# Protocol.net
KiCad netlist of a schematic drawn in Altium Designer
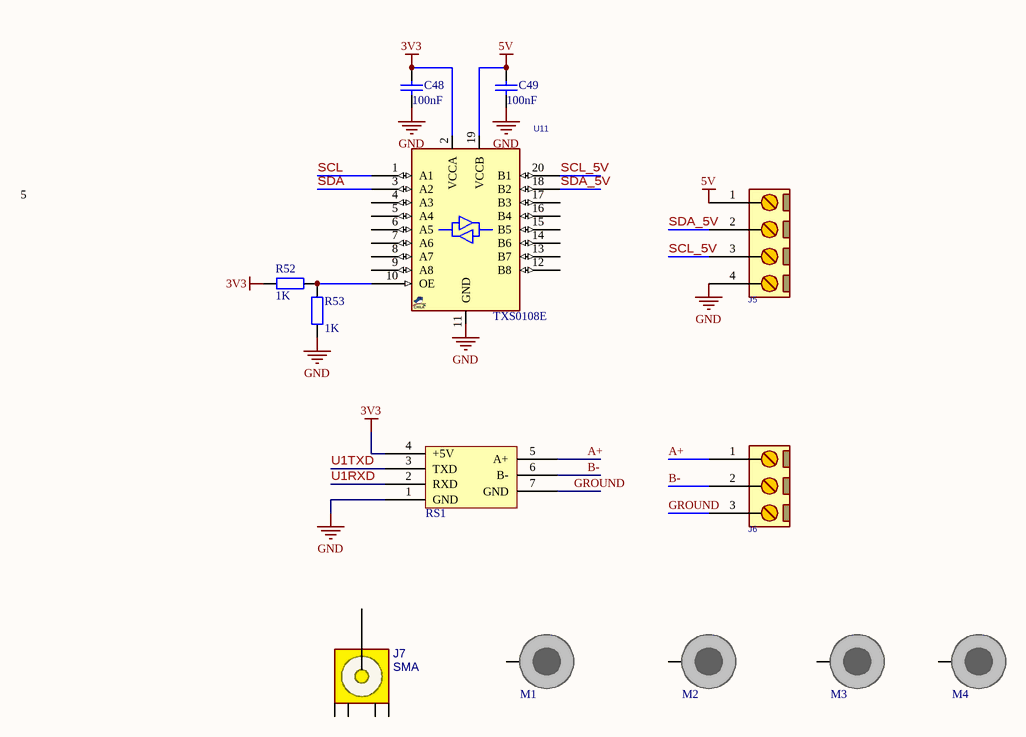
[diagram p0: Protocol.SchDoc]

(export (version "E")
  (design (tool "Eeschema 10.0.6"))
  (components
    (comp (ref "C48")
      (value "100nF_0603_1%")
      (footprint "tu 0603")
      (description "Capacitor, Ceramic, 50V")
      (fields (field (name "MA_HANG") "100nF"))
      (libsource (lib "THU VIEN SCH") (part "Tu 0603 470pF 50V 10%"))
    )
    (comp (ref "C49")
      (value "100nF_0603_1%")
      (footprint "tu 0603")
      (description "Capacitor, Ceramic, 50V")
      (fields (field (name "MA_HANG") "100nF"))
      (libsource (lib "THU VIEN SCH") (part "Tu 0603 470pF 50V 10%"))
    )
    (comp (ref "J5")
      (value "CONN_TB4")
      (footprint "TBB_4")
      (description "CONN, TERMINAL BLOCK, 5.08mm pitch")
      (libsource (lib "AH_Library") (part "CONN_TB4"))
    )
    (comp (ref "J6")
      (value "CONN_TB3")
      (footprint "TBB_3")
      (description "CONN, TERMINAL BLOCK, 5.08mm pitch")
      (libsource (lib "AH_Library") (part "CONN_TB3"))
    )
    (comp (ref "J7")
      (value "SMA")
      (footprint "SMA_RA")
      (description "CONN, RF, SMA, Right Angle")
      (fields (field (name "MANF_P#") "SMA-J-P-H-RA-TH1") (field (name "MANF") "Samtec"))
      (libsource (lib "AH_Library") (part "CONN_RF_SMA_RA"))
    )
    (comp (ref "M1")
      (value "DNP/MH")
      (footprint "SCMH_M3FT")
      (description "SCREW mouting, M3, 3.0mm diameter and 6.0mm, FlatHead")
      (libsource (lib "AH_Library") (part "SCMH_M3FT"))
    )
    (comp (ref "M2")
      (value "DNP/MH")
      (footprint "SCMH_M3FT")
      (description "SCREW mouting, M3, 3.0mm diameter and 6.0mm, FlatHead")
      (libsource (lib "AH_Library") (part "SCMH_M3FT"))
    )
    (comp (ref "M3")
      (value "DNP/MH")
      (footprint "SCMH_M3FT")
      (description "SCREW mouting, M3, 3.0mm diameter and 6.0mm, FlatHead")
      (libsource (lib "AH_Library") (part "SCMH_M3FT"))
    )
    (comp (ref "M4")
      (value "DNP/MH")
      (footprint "SCMH_M3FT")
      (description "SCREW mouting, M3, 3.0mm diameter and 6.0mm, FlatHead")
      (libsource (lib "AH_Library") (part "SCMH_M3FT"))
    )
    (comp (ref "R52")
      (value "1K_0603_1%")
      (footprint "tro smd 0603")
      (description "RES SMD 0603")
      (fields (field (name "MA_HANG") "1K"))
      (libsource (lib "THU VIEN SCH") (part "Tro 0603 5% 10k"))
    )
    (comp (ref "R53")
      (value "1K_0603_1%")
      (footprint "tro smd 0603")
      (description "RES SMD 0603")
      (fields (field (name "MA_HANG") "1K"))
      (libsource (lib "THU VIEN SCH") (part "Tro 0603 5% 10k"))
    )
    (comp (ref "RS1")
      (value "RS485_VISION2")
      (footprint "RS485 - Version2")
      (libsource (lib "TRANTHANHSANG") (part "RS485_VISION2"))
    )
    (comp (ref "U11")
      (value "TXS0108E")
      (footprint "SOG65_20")
      (description "Level Translator, Octal")
      (fields (field (name "MANF") "Texas Instruments") (field (name "MANF_P#") "TXS0108EPWR"))
      (libsource (lib "AH_Library") (part "TXS0108_SSOP20"))
    )
  )
  (nets
    (net (code "1") (name "/A+") (class "Default")
      (node (ref "J6") (pin "1") (pinfunction "1_1") (pintype "passive"))
      (node (ref "RS1") (pin "5") (pinfunction "A+_5") (pintype "passive"))
    )
    (net (code "2") (name "/B-") (class "Default")
      (node (ref "J6") (pin "2") (pinfunction "2_2") (pintype "passive"))
      (node (ref "RS1") (pin "6") (pinfunction "B-_6") (pintype "passive"))
    )
    (net (code "3") (name "/GROUND") (class "Default")
      (node (ref "J6") (pin "3") (pinfunction "3_3") (pintype "passive"))
      (node (ref "RS1") (pin "7") (pinfunction "GND_7") (pintype "passive"))
    )
    (net (code "4") (name "/SCL") (class "Default")
      (node (ref "U11") (pin "1") (pinfunction "A1_1") (pintype "bidirectional"))
    )
    (net (code "5") (name "/SCL_5V") (class "Default")
      (node (ref "J5") (pin "3") (pinfunction "3_3") (pintype "passive"))
      (node (ref "U11") (pin "20") (pinfunction "B1_20") (pintype "bidirectional"))
    )
    (net (code "6") (name "/SDA") (class "Default")
      (node (ref "U11") (pin "3") (pinfunction "A2_3") (pintype "bidirectional"))
    )
    (net (code "7") (name "/SDA_5V") (class "Default")
      (node (ref "J5") (pin "2") (pinfunction "2_2") (pintype "passive"))
      (node (ref "U11") (pin "18") (pinfunction "B2_18") (pintype "bidirectional"))
    )
    (net (code "8") (name "/U1RXD") (class "Default")
      (node (ref "RS1") (pin "2") (pinfunction "RXD_2") (pintype "passive"))
    )
    (net (code "9") (name "/U1TXD") (class "Default")
      (node (ref "RS1") (pin "3") (pinfunction "TXD_3") (pintype "passive"))
    )
    (net (code "10") (name "3V3") (class "Default")
      (node (ref "C48") (pin "1") (pinfunction "1_1") (pintype "passive"))
      (node (ref "R52") (pin "2") (pinfunction "2_2") (pintype "passive"))
      (node (ref "RS1") (pin "4") (pinfunction "+5V_4") (pintype "passive"))
      (node (ref "U11") (pin "2") (pinfunction "VCCA_2") (pintype "power_in"))
    )
    (net (code "11") (name "5V") (class "Default")
      (node (ref "C49") (pin "1") (pinfunction "1_1") (pintype "passive"))
      (node (ref "J5") (pin "1") (pinfunction "1_1") (pintype "passive"))
      (node (ref "U11") (pin "19") (pinfunction "VCCB_19") (pintype "power_in"))
    )
    (net (code "12") (name "GND") (class "Default")
      (node (ref "C48") (pin "2") (pinfunction "2_2") (pintype "passive"))
      (node (ref "C49") (pin "2") (pinfunction "2_2") (pintype "passive"))
      (node (ref "J5") (pin "4") (pinfunction "4_4") (pintype "passive"))
      (node (ref "R53") (pin "1") (pinfunction "1_1") (pintype "passive"))
      (node (ref "RS1") (pin "1") (pinfunction "GND_1") (pintype "passive"))
      (node (ref "U11") (pin "11") (pinfunction "GND_11") (pintype "power_in"))
    )
    (net (code "13") (name "Net-(U11-OE)") (class "Default")
      (node (ref "R52") (pin "1") (pinfunction "1_1") (pintype "passive"))
      (node (ref "R53") (pin "2") (pinfunction "2_2") (pintype "passive"))
      (node (ref "U11") (pin "10") (pinfunction "OE_10") (pintype "input"))
    )
    (net (code "14") (name "unconnected-(J7-G1-Pad2)") (class "Default")
      (node (ref "J7") (pin "2") (pinfunction "G1_2") (pintype "passive"))
    )
    (net (code "15") (name "unconnected-(J7-G2-Pad3)") (class "Default")
      (node (ref "J7") (pin "3") (pinfunction "G2_3") (pintype "passive"))
    )
    (net (code "16") (name "unconnected-(J7-G3-Pad4)") (class "Default")
      (node (ref "J7") (pin "4") (pinfunction "G3_4") (pintype "passive"))
    )
    (net (code "17") (name "unconnected-(J7-G4-Pad5)") (class "Default")
      (node (ref "J7") (pin "5") (pinfunction "G4_5") (pintype "passive"))
    )
    (net (code "18") (name "unconnected-(J7-SIG-Pad1)") (class "Default")
      (node (ref "J7") (pin "1") (pinfunction "SIG_1") (pintype "passive"))
    )
    (net (code "19") (name "unconnected-(M1-Pad1)") (class "Default")
      (node (ref "M1") (pin "1") (pinfunction "1_1") (pintype "passive"))
    )
    (net (code "20") (name "unconnected-(M2-Pad1)") (class "Default")
      (node (ref "M2") (pin "1") (pinfunction "1_1") (pintype "passive"))
    )
    (net (code "21") (name "unconnected-(M3-Pad1)") (class "Default")
      (node (ref "M3") (pin "1") (pinfunction "1_1") (pintype "passive"))
    )
    (net (code "22") (name "unconnected-(M4-Pad1)") (class "Default")
      (node (ref "M4") (pin "1") (pinfunction "1_1") (pintype "passive"))
    )
    (net (code "23") (name "unconnected-(U11-A3-Pad4)") (class "Default")
      (node (ref "U11") (pin "4") (pinfunction "A3_4") (pintype "bidirectional"))
    )
    (net (code "24") (name "unconnected-(U11-A4-Pad5)") (class "Default")
      (node (ref "U11") (pin "5") (pinfunction "A4_5") (pintype "bidirectional"))
    )
    (net (code "25") (name "unconnected-(U11-A5-Pad6)") (class "Default")
      (node (ref "U11") (pin "6") (pinfunction "A5_6") (pintype "bidirectional"))
    )
    (net (code "26") (name "unconnected-(U11-A6-Pad7)") (class "Default")
      (node (ref "U11") (pin "7") (pinfunction "A6_7") (pintype "bidirectional"))
    )
    (net (code "27") (name "unconnected-(U11-A7-Pad8)") (class "Default")
      (node (ref "U11") (pin "8") (pinfunction "A7_8") (pintype "bidirectional"))
    )
    (net (code "28") (name "unconnected-(U11-A8-Pad9)") (class "Default")
      (node (ref "U11") (pin "9") (pinfunction "A8_9") (pintype "bidirectional"))
    )
    (net (code "29") (name "unconnected-(U11-B3-Pad17)") (class "Default")
      (node (ref "U11") (pin "17") (pinfunction "B3_17") (pintype "bidirectional"))
    )
    (net (code "30") (name "unconnected-(U11-B4-Pad16)") (class "Default")
      (node (ref "U11") (pin "16") (pinfunction "B4_16") (pintype "bidirectional"))
    )
    (net (code "31") (name "unconnected-(U11-B5-Pad15)") (class "Default")
      (node (ref "U11") (pin "15") (pinfunction "B5_15") (pintype "bidirectional"))
    )
    (net (code "32") (name "unconnected-(U11-B6-Pad14)") (class "Default")
      (node (ref "U11") (pin "14") (pinfunction "B6_14") (pintype "bidirectional"))
    )
    (net (code "33") (name "unconnected-(U11-B7-Pad13)") (class "Default")
      (node (ref "U11") (pin "13") (pinfunction "B7_13") (pintype "bidirectional"))
    )
    (net (code "34") (name "unconnected-(U11-B8-Pad12)") (class "Default")
      (node (ref "U11") (pin "12") (pinfunction "B8_12") (pintype "bidirectional"))
    )
  )
)
